# Internal_Power_schematic.net
KiCad netlist of a schematic drawn in Altium Designer
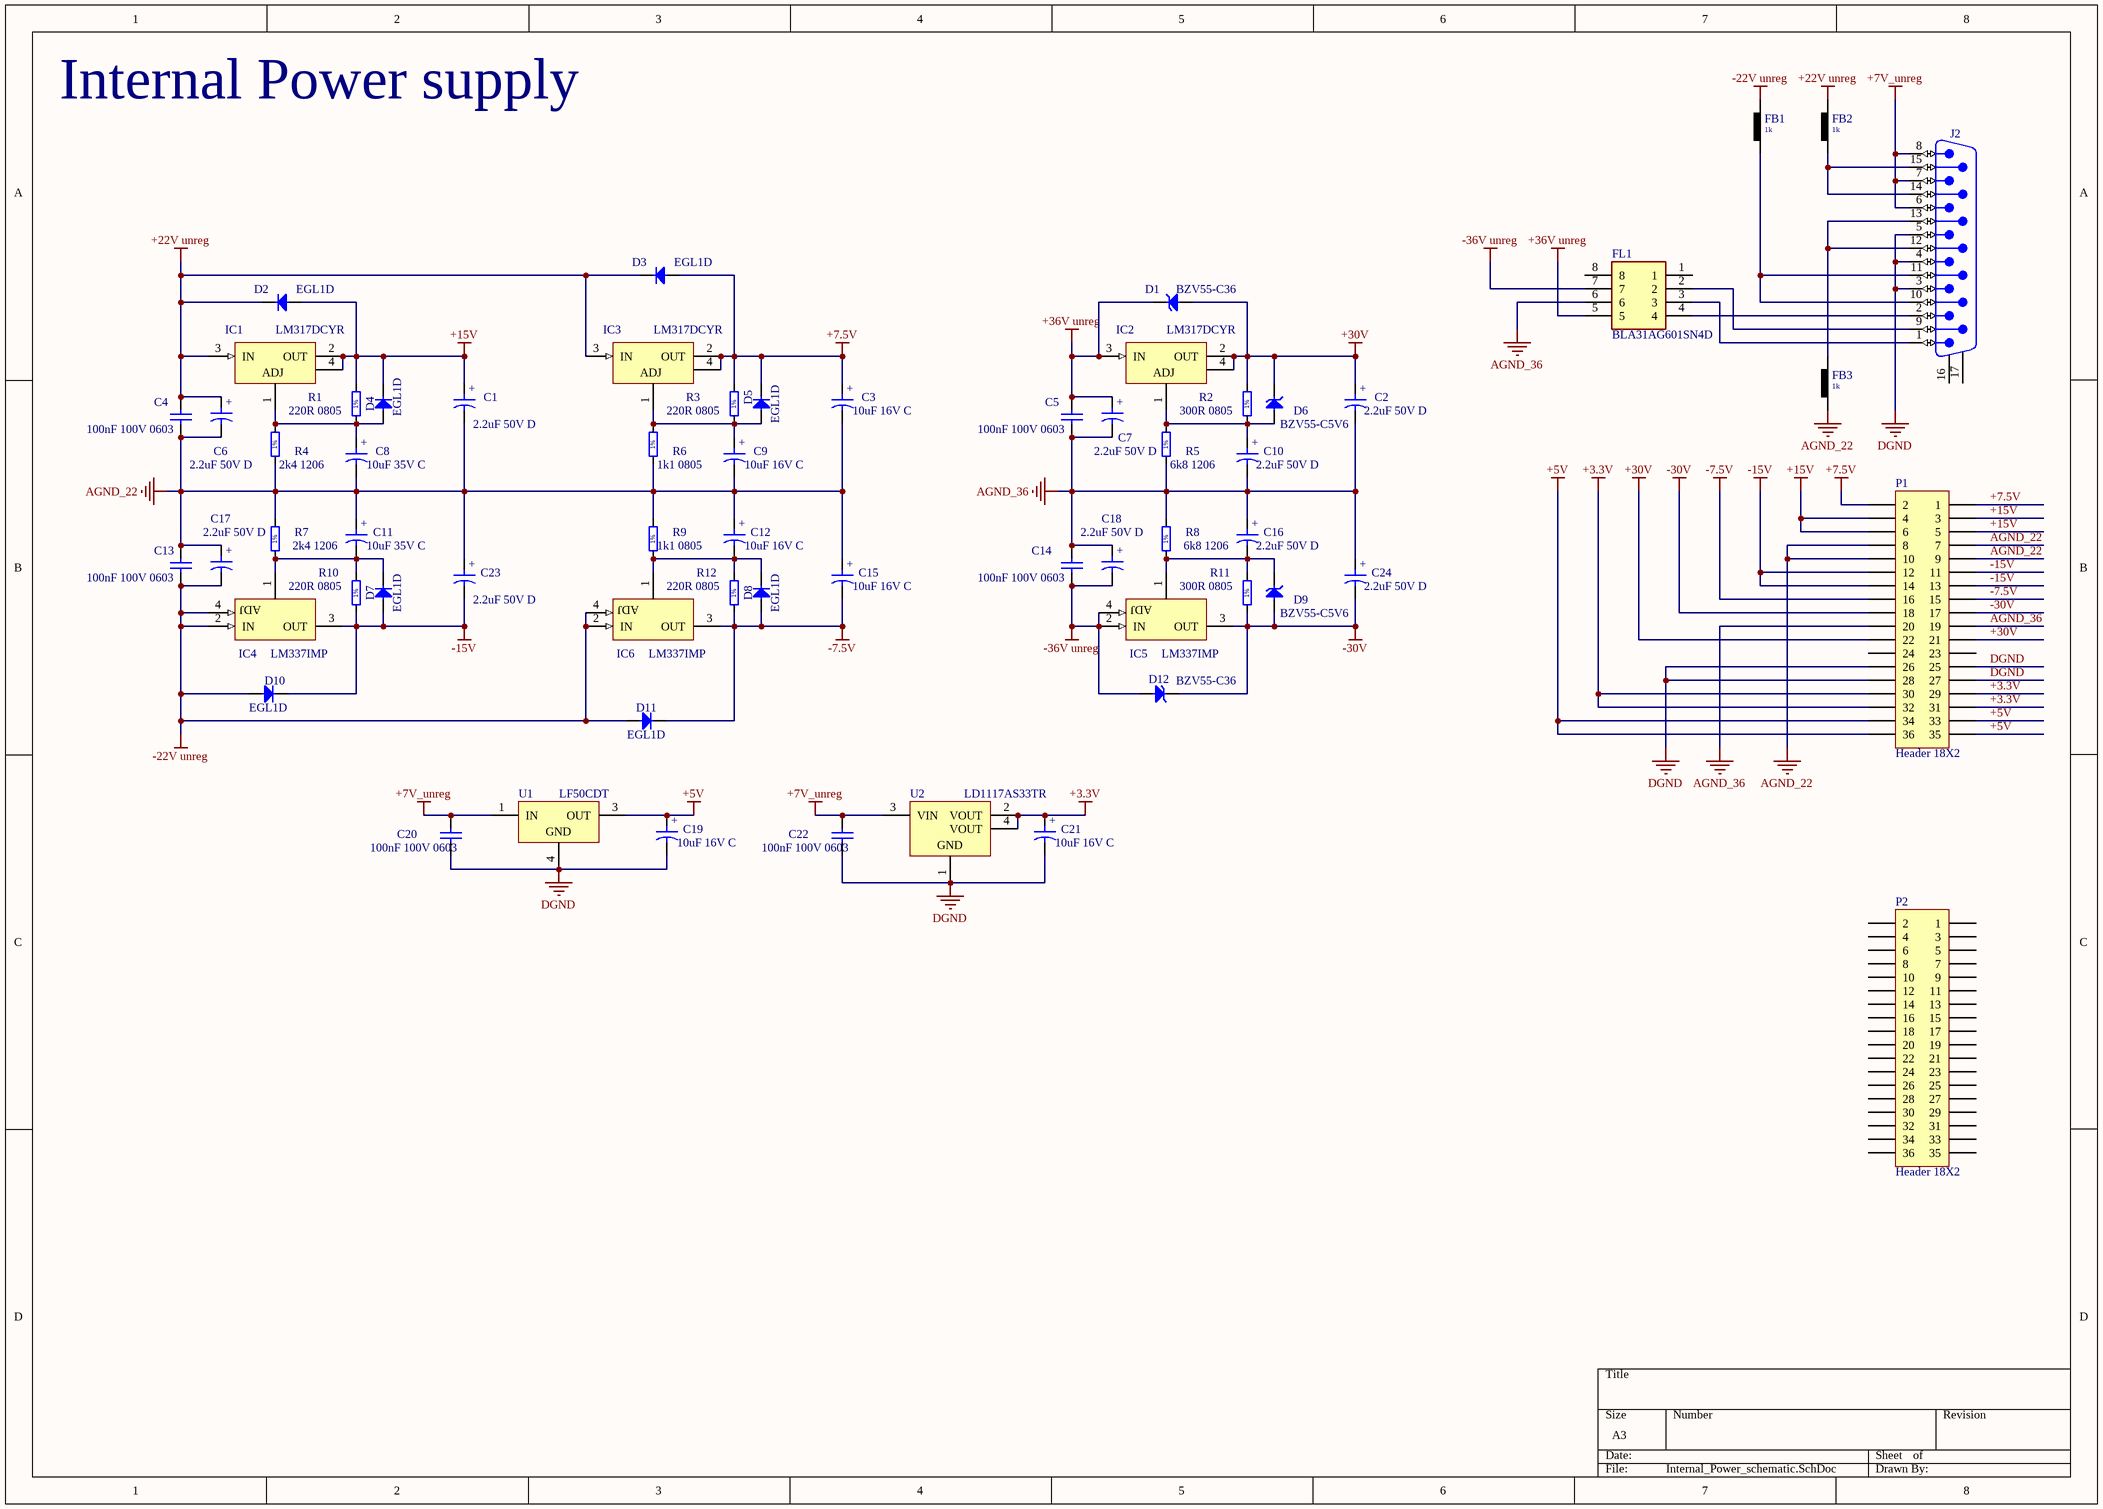
[diagram p0: Internal_Power_schematic.SchDoc]

(export (version "E")
  (design (tool "Eeschema 10.0.6"))
  (components
    (comp (ref "C1")
      (value "2.2uF 50V D")
      (footprint "CAPMP7343X310N")
      (description "Polarised capacitor")
      (fields
        (field (name "PART NUMBER") "CTE7343-31_22UF_35V_20%_LESR0400")
        (field (name "VOLTAGE") "35V")
        (field (name "AUTHOR") "CERN DEM MR")
      )
      (libsource (lib "Capacitors") (part "Capacitor - polarized"))
    )
    (comp (ref "C2")
      (value "2.2uF 50V D")
      (footprint "CAPMP7343X310N")
      (description "Polarised capacitor")
      (fields
        (field (name "PART NUMBER") "CTE7343-31_22UF_35V_20%_LESR0400")
        (field (name "VOLTAGE") "35V")
        (field (name "AUTHOR") "CERN DEM MR")
      )
      (libsource (lib "Capacitors") (part "Capacitor - polarized"))
    )
    (comp (ref "C3")
      (value "10uF 16V C")
      (footprint "CAPMP6032X280N")
      (description "Polarised capacitor")
      (fields
        (field (name "PART NUMBER") "CTE6032-28_10UF_25V_10%_LESR0500")
        (field (name "VOLTAGE") "25V")
        (field (name "AUTHOR") "CERN DEM JLC")
      )
      (libsource (lib "Capacitors") (part "Capacitor - polarized"))
    )
    (comp (ref "C4")
      (value "100nF 100V 0603")
      (footprint "1608[0603]_CAP")
      (description "Capacitor (Semiconductor SIM Model)")
      (fields (field (name "PUBLISHER") "Altium Limited"))
      (libsource (lib "Miscellaneous Devices") (part "Cap Semi"))
    )
    (comp (ref "C5")
      (value "100nF 100V 0603")
      (footprint "1608[0603]_CAP")
      (description "Capacitor (Semiconductor SIM Model)")
      (fields (field (name "PUBLISHER") "Altium Limited"))
      (libsource (lib "Miscellaneous Devices") (part "Cap Semi"))
    )
    (comp (ref "C6")
      (value "2.2uF 50V D")
      (footprint "CAPMP7343X310N")
      (description "Polarised capacitor")
      (fields
        (field (name "PART NUMBER") "CTE7343-31_22UF_35V_20%_LESR0400")
        (field (name "VOLTAGE") "35V")
        (field (name "AUTHOR") "CERN DEM MR")
      )
      (libsource (lib "Capacitors") (part "Capacitor - polarized"))
    )
    (comp (ref "C7")
      (value "2.2uF 50V D")
      (footprint "CAPMP7343X310N")
      (description "Polarised capacitor")
      (fields
        (field (name "PART NUMBER") "CTE7343-31_22UF_35V_20%_LESR0400")
        (field (name "VOLTAGE") "35V")
        (field (name "AUTHOR") "CERN DEM MR")
      )
      (libsource (lib "Capacitors") (part "Capacitor - polarized"))
    )
    (comp (ref "C8")
      (value "10uF 35V C")
      (footprint "CAPMP6032X280N")
      (description "Polarised capacitor")
      (fields
        (field (name "PART NUMBER") "CTE6032-28_10UF_25V_10%_LESR0500")
        (field (name "VOLTAGE") "25V")
        (field (name "AUTHOR") "CERN DEM JLC")
      )
      (libsource (lib "Capacitors") (part "Capacitor - polarized"))
    )
    (comp (ref "C9")
      (value "10uF 16V C")
      (footprint "CAPMP6032X280N")
      (description "Polarised capacitor")
      (fields
        (field (name "PART NUMBER") "CTE6032-28_10UF_25V_10%_LESR0500")
        (field (name "VOLTAGE") "25V")
        (field (name "AUTHOR") "CERN DEM JLC")
      )
      (libsource (lib "Capacitors") (part "Capacitor - polarized"))
    )
    (comp (ref "C10")
      (value "2.2uF 50V D")
      (footprint "CAPMP7343X310N")
      (description "Polarised capacitor")
      (fields
        (field (name "PART NUMBER") "CTE7343-31_22UF_35V_20%_LESR0400")
        (field (name "VOLTAGE") "35V")
        (field (name "AUTHOR") "CERN DEM MR")
      )
      (libsource (lib "Capacitors") (part "Capacitor - polarized"))
    )
    (comp (ref "C11")
      (value "10uF 35V C")
      (footprint "CAPMP6032X280N")
      (description "Polarised capacitor")
      (fields
        (field (name "PART NUMBER") "CTE6032-28_10UF_25V_10%_LESR0500")
        (field (name "VOLTAGE") "25V")
        (field (name "AUTHOR") "CERN DEM JLC")
      )
      (libsource (lib "Capacitors") (part "Capacitor - polarized"))
    )
    (comp (ref "C12")
      (value "10uF 16V C")
      (footprint "CAPMP6032X280N")
      (description "Polarised capacitor")
      (fields
        (field (name "PART NUMBER") "CTE6032-28_10UF_25V_10%_LESR0500")
        (field (name "VOLTAGE") "25V")
        (field (name "AUTHOR") "CERN DEM JLC")
      )
      (libsource (lib "Capacitors") (part "Capacitor - polarized"))
    )
    (comp (ref "C13")
      (value "100nF 100V 0603")
      (footprint "1608[0603]_CAP")
      (description "Capacitor (Semiconductor SIM Model)")
      (fields (field (name "PUBLISHER") "Altium Limited"))
      (libsource (lib "Miscellaneous Devices") (part "Cap Semi"))
    )
    (comp (ref "C14")
      (value "100nF 100V 0603")
      (footprint "1608[0603]_CAP")
      (description "Capacitor (Semiconductor SIM Model)")
      (fields (field (name "PUBLISHER") "Altium Limited"))
      (libsource (lib "Miscellaneous Devices") (part "Cap Semi"))
    )
    (comp (ref "C15")
      (value "10uF 16V C")
      (footprint "CAPMP6032X280N")
      (description "Polarised capacitor")
      (fields
        (field (name "PART NUMBER") "CTE6032-28_10UF_25V_10%_LESR0500")
        (field (name "VOLTAGE") "25V")
        (field (name "AUTHOR") "CERN DEM JLC")
      )
      (libsource (lib "Capacitors") (part "Capacitor - polarized"))
    )
    (comp (ref "C16")
      (value "2.2uF 50V D")
      (footprint "CAPMP7343X310N")
      (description "Polarised capacitor")
      (fields
        (field (name "PART NUMBER") "CTE7343-31_22UF_35V_20%_LESR0400")
        (field (name "VOLTAGE") "35V")
        (field (name "AUTHOR") "CERN DEM MR")
      )
      (libsource (lib "Capacitors") (part "Capacitor - polarized"))
    )
    (comp (ref "C17")
      (value "2.2uF 50V D")
      (footprint "CAPMP7343X310N")
      (description "Polarised capacitor")
      (fields
        (field (name "PART NUMBER") "CTE7343-31_22UF_35V_20%_LESR0400")
        (field (name "VOLTAGE") "35V")
        (field (name "AUTHOR") "CERN DEM MR")
      )
      (libsource (lib "Capacitors") (part "Capacitor - polarized"))
    )
    (comp (ref "C18")
      (value "2.2uF 50V D")
      (footprint "CAPMP7343X310N")
      (description "Polarised capacitor")
      (fields
        (field (name "PART NUMBER") "CTE7343-31_22UF_35V_20%_LESR0400")
        (field (name "VOLTAGE") "35V")
        (field (name "AUTHOR") "CERN DEM MR")
      )
      (libsource (lib "Capacitors") (part "Capacitor - polarized"))
    )
    (comp (ref "C19")
      (value "10uF 16V C")
      (footprint "CAPMP6032X280N")
      (description "Polarised capacitor")
      (fields
        (field (name "PART NUMBER") "CTE6032-28_10UF_25V_10%_LESR0500")
        (field (name "VOLTAGE") "25V")
        (field (name "AUTHOR") "CERN DEM JLC")
      )
      (libsource (lib "Capacitors") (part "Capacitor - polarized"))
    )
    (comp (ref "C20")
      (value "100nF 100V 0603")
      (footprint "1608[0603]_CAP")
      (description "Capacitor (Semiconductor SIM Model)")
      (fields (field (name "PUBLISHER") "Altium Limited"))
      (libsource (lib "Miscellaneous Devices") (part "Cap Semi"))
    )
    (comp (ref "C21")
      (value "10uF 16V C")
      (footprint "CAPMP6032X280N")
      (description "Polarised capacitor")
      (fields
        (field (name "PART NUMBER") "CTE6032-28_10UF_25V_10%_LESR0500")
        (field (name "VOLTAGE") "25V")
        (field (name "AUTHOR") "CERN DEM JLC")
      )
      (libsource (lib "Capacitors") (part "Capacitor - polarized"))
    )
    (comp (ref "C22")
      (value "100nF 100V 0603")
      (footprint "1608[0603]_CAP")
      (description "Capacitor (Semiconductor SIM Model)")
      (fields (field (name "PUBLISHER") "Altium Limited"))
      (libsource (lib "Miscellaneous Devices") (part "Cap Semi"))
    )
    (comp (ref "C23")
      (value "2.2uF 50V D")
      (footprint "CAPMP7343X310N")
      (description "Polarised capacitor")
      (fields
        (field (name "PART NUMBER") "CTE7343-31_22UF_35V_20%_LESR0400")
        (field (name "VOLTAGE") "35V")
        (field (name "AUTHOR") "CERN DEM MR")
      )
      (libsource (lib "Capacitors") (part "Capacitor - polarized"))
    )
    (comp (ref "C24")
      (value "2.2uF 50V D")
      (footprint "CAPMP7343X310N")
      (description "Polarised capacitor")
      (fields
        (field (name "PART NUMBER") "CTE7343-31_22UF_35V_20%_LESR0400")
        (field (name "VOLTAGE") "35V")
        (field (name "AUTHOR") "CERN DEM MR")
      )
      (libsource (lib "Capacitors") (part "Capacitor - polarized"))
    )
    (comp (ref "D1")
      (value "BZV55-C36")
      (footprint "DIOMELF3515N")
      (description "Zener Diode")
      (fields
        (field (name "PART NUMBER") "BZV55-C12")
        (field (name "VOLTAGE") "12V")
        (field (name "AUTHOR") "CERN DEM MR")
      )
      (libsource (lib "ICs And Semiconductors") (part "Diode Zener"))
    )
    (comp (ref "D2")
      (value "EGL1D")
      (footprint "DIOMELF3515N")
      (description "Diode")
      (fields
        (field (name "PART NUMBER") "PMLL4148L")
        (field (name "VOLTAGE") "75V")
        (field (name "AUTHOR") "CERN DEM JLC")
      )
      (libsource (lib "ICs And Semiconductors") (part "Diode"))
    )
    (comp (ref "D3")
      (value "EGL1D")
      (footprint "DIOMELF3515N")
      (description "Diode")
      (fields
        (field (name "PART NUMBER") "PMLL4148L")
        (field (name "VOLTAGE") "75V")
        (field (name "AUTHOR") "CERN DEM JLC")
      )
      (libsource (lib "ICs And Semiconductors") (part "Diode"))
    )
    (comp (ref "D4")
      (value "EGL1D")
      (footprint "DIOMELF3515N")
      (description "Diode")
      (fields
        (field (name "PART NUMBER") "PMLL4148L")
        (field (name "VOLTAGE") "75V")
        (field (name "AUTHOR") "CERN DEM JLC")
      )
      (libsource (lib "ICs And Semiconductors") (part "Diode"))
    )
    (comp (ref "D5")
      (value "EGL1D")
      (footprint "DIOMELF3515N")
      (description "Diode")
      (fields
        (field (name "PART NUMBER") "PMLL4148L")
        (field (name "VOLTAGE") "75V")
        (field (name "AUTHOR") "CERN DEM JLC")
      )
      (libsource (lib "ICs And Semiconductors") (part "Diode"))
    )
    (comp (ref "D6")
      (value "BZV55-C5V6")
      (footprint "DIOMELF3515N")
      (description "Zener Diode")
      (fields
        (field (name "PART NUMBER") "BZV55-C12")
        (field (name "VOLTAGE") "12V")
        (field (name "AUTHOR") "CERN DEM MR")
      )
      (libsource (lib "ICs And Semiconductors") (part "Diode Zener"))
    )
    (comp (ref "D7")
      (value "EGL1D")
      (footprint "DIOMELF3515N")
      (description "Diode")
      (fields
        (field (name "PART NUMBER") "PMLL4148L")
        (field (name "VOLTAGE") "75V")
        (field (name "AUTHOR") "CERN DEM JLC")
      )
      (libsource (lib "ICs And Semiconductors") (part "Diode"))
    )
    (comp (ref "D8")
      (value "EGL1D")
      (footprint "DIOMELF3515N")
      (description "Diode")
      (fields
        (field (name "PART NUMBER") "PMLL4148L")
        (field (name "VOLTAGE") "75V")
        (field (name "AUTHOR") "CERN DEM JLC")
      )
      (libsource (lib "ICs And Semiconductors") (part "Diode"))
    )
    (comp (ref "D9")
      (value "BZV55-C5V6")
      (footprint "DIOMELF3515N")
      (description "Zener Diode")
      (fields
        (field (name "PART NUMBER") "BZV55-C12")
        (field (name "VOLTAGE") "12V")
        (field (name "AUTHOR") "CERN DEM MR")
      )
      (libsource (lib "ICs And Semiconductors") (part "Diode Zener"))
    )
    (comp (ref "D10")
      (value "EGL1D")
      (footprint "DIOMELF3515N")
      (description "Diode")
      (fields
        (field (name "PART NUMBER") "PMLL4148L")
        (field (name "VOLTAGE") "75V")
        (field (name "AUTHOR") "CERN DEM JLC")
      )
      (libsource (lib "ICs And Semiconductors") (part "Diode"))
    )
    (comp (ref "D11")
      (value "EGL1D")
      (footprint "DIOMELF3515N")
      (description "Diode")
      (fields
        (field (name "PART NUMBER") "PMLL4148L")
        (field (name "VOLTAGE") "75V")
        (field (name "AUTHOR") "CERN DEM JLC")
      )
      (libsource (lib "ICs And Semiconductors") (part "Diode"))
    )
    (comp (ref "D12")
      (value "BZV55-C36")
      (footprint "DIOMELF3515N")
      (description "Zener Diode")
      (fields
        (field (name "PART NUMBER") "BZV55-C12")
        (field (name "VOLTAGE") "12V")
        (field (name "AUTHOR") "CERN DEM MR")
      )
      (libsource (lib "ICs And Semiconductors") (part "Diode Zener"))
    )
    (comp (ref "FB1")
      (value "1k")
      (footprint "FB1206")
      (description "1206 1.5A 0.08ohm")
      (libsource (lib "SMD-RCL") (part "Chip FB BLM31P"))
    )
    (comp (ref "FB2")
      (value "1k")
      (footprint "FB1206")
      (description "1206 1.5A 0.08ohm")
      (libsource (lib "SMD-RCL") (part "Chip FB BLM31P"))
    )
    (comp (ref "FB3")
      (value "1k")
      (footprint "FB1206")
      (description "1206 1.5A 0.08ohm")
      (libsource (lib "SMD-RCL") (part "Chip FB BLM31P"))
    )
    (comp (ref "FL1")
      (value "BLA31AG601SN4D")
      (footprint "SamacSys:BLA31AG102SN4D")
      (description "Filter")
      (fields (field (name "MOUSER PART NUMBER") "81-BLA3216A601SG4"))
      (libsource (lib "SamacSys") (part "BLA31AG601SN4D"))
    )
    (comp (ref "IC1")
      (value "LM317DCYR")
      (footprint "SOT230P700X180-4N")
      (description "3-Terminal Regulator 1=Adj 2=OUT 3=IN 4=OUT")
      (fields
        (field (name "PART NUMBER") "LM317EMP")
        (field (name "MANUFACTURER") "TEXAS INSTRUMENTS")
        (field (name "AUTHOR") "CERN DEM JLC")
      )
      (libsource (lib "ICs And Semiconductors") (part "REG3+1 1ADJ-2OUT-3IN+4OUT"))
    )
    (comp (ref "IC2")
      (value "LM317DCYR")
      (footprint "SOT230P700X180-4N")
      (description "3-Terminal Regulator 1=Adj 2=OUT 3=IN 4=OUT")
      (fields
        (field (name "PART NUMBER") "LM317EMP")
        (field (name "MANUFACTURER") "TEXAS INSTRUMENTS")
        (field (name "AUTHOR") "CERN DEM JLC")
      )
      (libsource (lib "ICs And Semiconductors") (part "REG3+1 1ADJ-2OUT-3IN+4OUT"))
    )
    (comp (ref "IC3")
      (value "LM317DCYR")
      (footprint "SOT230P700X180-4N")
      (description "3-Terminal Regulator 1=Adj 2=OUT 3=IN 4=OUT")
      (fields
        (field (name "PART NUMBER") "LM317EMP")
        (field (name "MANUFACTURER") "TEXAS INSTRUMENTS")
        (field (name "AUTHOR") "CERN DEM JLC")
      )
      (libsource (lib "ICs And Semiconductors") (part "REG3+1 1ADJ-2OUT-3IN+4OUT"))
    )
    (comp (ref "IC4")
      (value "LM337IMP")
      (footprint "SOT230P700X180-4N")
      (description "3-Terminal Regulator 1=Adj 2=IN 3=OUT 4=IN")
      (fields
        (field (name "PART NUMBER") "LM337IMP/NOPB")
        (field (name "MANUFACTURER") "TEXAS INSTRUMENTS")
        (field (name "AUTHOR") "CERN DEM JLC")
      )
      (libsource (lib "ICs And Semiconductors") (part "REG3+1 1ADJ-2IN-3OUT+4IN"))
    )
    (comp (ref "IC5")
      (value "LM337IMP")
      (footprint "SOT230P700X180-4N")
      (description "3-Terminal Regulator 1=Adj 2=IN 3=OUT 4=IN")
      (fields
        (field (name "PART NUMBER") "LM337IMP/NOPB")
        (field (name "MANUFACTURER") "TEXAS INSTRUMENTS")
        (field (name "AUTHOR") "CERN DEM JLC")
      )
      (libsource (lib "ICs And Semiconductors") (part "REG3+1 1ADJ-2IN-3OUT+4IN"))
    )
    (comp (ref "IC6")
      (value "LM337IMP")
      (footprint "SOT230P700X180-4N")
      (description "3-Terminal Regulator 1=Adj 2=IN 3=OUT 4=IN")
      (fields
        (field (name "PART NUMBER") "LM337IMP/NOPB")
        (field (name "MANUFACTURER") "TEXAS INSTRUMENTS")
        (field (name "AUTHOR") "CERN DEM JLC")
      )
      (libsource (lib "ICs And Semiconductors") (part "REG3+1 1ADJ-2IN-3OUT+4IN"))
    )
    (comp (ref "J2")
      (value "D-Sub")
      (footprint "DB15_PCB_AL;UMINIUM")
      (description "Connector D-sub 15 Male")
      (fields
        (field (name "PART NUMBER") "AMPHENOL_L117DFA15P1ATN")
        (field (name "MANUFACTURER") "AMPHENOL")
        (field (name "AUTHOR") "CERN DEM JLC")
      )
      (libsource (lib "Connectors") (part "Connector D-sub 15 Male"))
    )
    (comp (ref "P1")
      (value "Header 18X2")
      (footprint "18x2 header aluminium")
      (description "Header, 18-Pin, Dual row")
      (fields (field (name "PUBLISHER") "Altium Limited"))
      (libsource (lib "Miscellaneous Connectors") (part "Header 18X2"))
    )
    (comp (ref "P2")
      (value "Header 18X2")
      (footprint "18x2 header aluminium")
      (description "Header, 18-Pin, Dual row")
      (fields (field (name "PUBLISHER") "Altium Limited"))
      (libsource (lib "Miscellaneous Connectors") (part "Header 18X2"))
    )
    (comp (ref "R1")
      (value "220R 0805")
      (footprint "RESC2012X60N")
      (description "Resistor - 1%")
      (fields
        (field (name "PART NUMBER") "R0805_220R_1%_0.125W_100PPM")
        (field (name "POWER") "0.125W")
        (field (name "AUTHOR") "CERN DEM JLC")
      )
      (libsource (lib "Resistors") (part "Resistor - 1%"))
    )
    (comp (ref "R2")
      (value "300R 0805")
      (footprint "RESC2012X60N")
      (description "Resistor - 1%")
      (fields
        (field (name "PART NUMBER") "R0805_220R_1%_0.125W_100PPM")
        (field (name "POWER") "0.125W")
        (field (name "AUTHOR") "CERN DEM JLC")
      )
      (libsource (lib "Resistors") (part "Resistor - 1%"))
    )
    (comp (ref "R3")
      (value "220R 0805")
      (footprint "RESC2012X60N")
      (description "Resistor - 1%")
      (fields
        (field (name "PART NUMBER") "R0805_220R_1%_0.125W_100PPM")
        (field (name "POWER") "0.125W")
        (field (name "AUTHOR") "CERN DEM JLC")
      )
      (libsource (lib "Resistors") (part "Resistor - 1%"))
    )
    (comp (ref "R4")
      (value "2k4 1206")
      (footprint "RESC3216X65N")
      (description "Resistor - 1%")
      (fields
        (field (name "PART NUMBER") "R1206_2K4_1%_0.25W_100PPM")
        (field (name "POWER") "0.25W")
        (field (name "AUTHOR") "CERN DEM JLC")
      )
      (libsource (lib "Resistors") (part "Resistor - 1%"))
    )
    (comp (ref "R5")
      (value "6k8 1206")
      (footprint "RESC3216X65N")
      (description "Resistor - 1%")
      (fields
        (field (name "PART NUMBER") "R1206_2K4_1%_0.25W_100PPM")
        (field (name "POWER") "0.25W")
        (field (name "AUTHOR") "CERN DEM JLC")
      )
      (libsource (lib "Resistors") (part "Resistor - 1%"))
    )
    (comp (ref "R6")
      (value "1k1 0805")
      (footprint "RESC2012X60N")
      (description "Resistor - 1%")
      (fields
        (field (name "PART NUMBER") "R0805_1K1_1%_0.125W_100PPM")
        (field (name "POWER") "0.125W")
        (field (name "AUTHOR") "CERN DEM JLC")
      )
      (libsource (lib "Resistors") (part "Resistor - 1%"))
    )
    (comp (ref "R7")
      (value "2k4 1206")
      (footprint "RESC3216X65N")
      (description "Resistor - 1%")
      (fields
        (field (name "PART NUMBER") "R1206_2K4_1%_0.25W_100PPM")
        (field (name "POWER") "0.25W")
        (field (name "AUTHOR") "CERN DEM JLC")
      )
      (libsource (lib "Resistors") (part "Resistor - 1%"))
    )
    (comp (ref "R8")
      (value "6k8 1206")
      (footprint "RESC3216X65N")
      (description "Resistor - 1%")
      (fields
        (field (name "PART NUMBER") "R1206_2K4_1%_0.25W_100PPM")
        (field (name "POWER") "0.25W")
        (field (name "AUTHOR") "CERN DEM JLC")
      )
      (libsource (lib "Resistors") (part "Resistor - 1%"))
    )
    (comp (ref "R9")
      (value "1k1 0805")
      (footprint "RESC2012X60N")
      (description "Resistor - 1%")
      (fields
        (field (name "PART NUMBER") "R0805_1K1_1%_0.125W_100PPM")
        (field (name "POWER") "0.125W")
        (field (name "AUTHOR") "CERN DEM JLC")
      )
      (libsource (lib "Resistors") (part "Resistor - 1%"))
    )
    (comp (ref "R10")
      (value "220R 0805")
      (footprint "RESC2012X60N")
      (description "Resistor - 1%")
      (fields
        (field (name "PART NUMBER") "R0805_220R_1%_0.125W_100PPM")
        (field (name "POWER") "0.125W")
        (field (name "AUTHOR") "CERN DEM JLC")
      )
      (libsource (lib "Resistors") (part "Resistor - 1%"))
    )
    (comp (ref "R11")
      (value "300R 0805")
      (footprint "RESC2012X60N")
      (description "Resistor - 1%")
      (fields
        (field (name "PART NUMBER") "R0805_220R_1%_0.125W_100PPM")
        (field (name "POWER") "0.125W")
        (field (name "AUTHOR") "CERN DEM JLC")
      )
      (libsource (lib "Resistors") (part "Resistor - 1%"))
    )
    (comp (ref "R12")
      (value "220R 0805")
      (footprint "RESC2012X60N")
      (description "Resistor - 1%")
      (fields
        (field (name "PART NUMBER") "R0805_220R_1%_0.125W_100PPM")
        (field (name "POWER") "0.125W")
        (field (name "AUTHOR") "CERN DEM JLC")
      )
      (libsource (lib "Resistors") (part "Resistor - 1%"))
    )
    (comp (ref "U1")
      (value "LF50CDT")
      (footprint "TO-252")
      (description "500mA, Very Low Drop (0.45V) Voltage Regulator")
      (fields (field (name "PUBLISHER") "Altium Limited"))
      (libsource (lib "ST Power Mgt Voltage Regulator") (part "LF50CDT"))
    )
    (comp (ref "U2")
      (value "LD1117AS33TR")
      (footprint "SOT-223_N")
      (description "1A, Low Drop Positive Voltage Regulator, 3.3V, 4-Pin SOT-223, Tape and Reel")
      (libsource (lib "STMicroelectronics Power Management Linear Regulator") (part "LD1117AS33TR"))
    )
  )
  (nets
    (net (code "1") (name "+3.3V") (class "Default")
      (node (ref "C21") (pin "1") (pinfunction "1_1") (pintype "passive"))
      (node (ref "P1") (pin "29") (pinfunction "29_29") (pintype "passive"))
      (node (ref "P1") (pin "30") (pinfunction "30_30") (pintype "passive"))
      (node (ref "P1") (pin "31") (pinfunction "31_31") (pintype "passive"))
      (node (ref "P1") (pin "32") (pinfunction "32_32") (pintype "passive"))
      (node (ref "U2") (pin "2") (pinfunction "VOUT_2") (pintype "power_in"))
      (node (ref "U2") (pin "4") (pinfunction "VOUT_4") (pintype "power_in"))
    )
    (net (code "2") (name "+5V") (class "Default")
      (node (ref "C19") (pin "1") (pinfunction "1_1") (pintype "passive"))
      (node (ref "P1") (pin "33") (pinfunction "33_33") (pintype "passive"))
      (node (ref "P1") (pin "34") (pinfunction "34_34") (pintype "passive"))
      (node (ref "P1") (pin "35") (pinfunction "35_35") (pintype "passive"))
      (node (ref "P1") (pin "36") (pinfunction "36_36") (pintype "passive"))
      (node (ref "U1") (pin "3") (pinfunction "OUT_3") (pintype "power_in"))
    )
    (net (code "3") (name "+7.5V") (class "Default")
      (node (ref "C3") (pin "1") (pinfunction "1_1") (pintype "passive"))
      (node (ref "D3") (pin "2") (pinfunction "A_2") (pintype "passive"))
      (node (ref "D5") (pin "1") (pinfunction "C_1") (pintype "passive"))
      (node (ref "IC3") (pin "2") (pinfunction "OUT_2") (pintype "power_in"))
      (node (ref "IC3") (pin "4") (pinfunction "OUT_4") (pintype "power_in"))
      (node (ref "P1") (pin "1") (pinfunction "1_1") (pintype "passive"))
      (node (ref "P1") (pin "2") (pinfunction "2_2") (pintype "passive"))
      (node (ref "R3") (pin "2") (pinfunction "2_2") (pintype "passive"))
    )
    (net (code "4") (name "+7V_unreg") (class "Default")
      (node (ref "C20") (pin "1") (pinfunction "1_1") (pintype "passive"))
      (node (ref "C22") (pin "1") (pinfunction "1_1") (pintype "passive"))
      (node (ref "J2") (pin "6") (pinfunction "6_6") (pintype "bidirectional"))
      (node (ref "J2") (pin "7") (pinfunction "7_7") (pintype "bidirectional"))
      (node (ref "J2") (pin "8") (pinfunction "8_8") (pintype "bidirectional"))
      (node (ref "U1") (pin "1") (pinfunction "IN_1") (pintype "power_in"))
      (node (ref "U2") (pin "3") (pinfunction "VIN_3") (pintype "power_in"))
    )
    (net (code "5") (name "+15V") (class "Default")
      (node (ref "C1") (pin "1") (pinfunction "1_1") (pintype "passive"))
      (node (ref "D2") (pin "2") (pinfunction "A_2") (pintype "passive"))
      (node (ref "D4") (pin "1") (pinfunction "C_1") (pintype "passive"))
      (node (ref "IC1") (pin "2") (pinfunction "OUT_2") (pintype "power_in"))
      (node (ref "IC1") (pin "4") (pinfunction "OUT_4") (pintype "power_in"))
      (node (ref "P1") (pin "3") (pinfunction "3_3") (pintype "passive"))
      (node (ref "P1") (pin "4") (pinfunction "4_4") (pintype "passive"))
      (node (ref "P1") (pin "5") (pinfunction "5_5") (pintype "passive"))
      (node (ref "P1") (pin "6") (pinfunction "6_6") (pintype "passive"))
      (node (ref "R1") (pin "2") (pinfunction "2_2") (pintype "passive"))
    )
    (net (code "6") (name "+22V unreg") (class "Default")
      (node (ref "C4") (pin "1") (pinfunction "1_1") (pintype "passive"))
      (node (ref "C6") (pin "1") (pinfunction "1_1") (pintype "passive"))
      (node (ref "D2") (pin "1") (pinfunction "C_1") (pintype "passive"))
      (node (ref "D3") (pin "1") (pinfunction "C_1") (pintype "passive"))
      (node (ref "FB2") (pin "2") (pinfunction "2_2") (pintype "passive"))
      (node (ref "IC1") (pin "3") (pinfunction "IN_3") (pintype "input"))
      (node (ref "IC3") (pin "3") (pinfunction "IN_3") (pintype "input"))
    )
    (net (code "7") (name "+30V") (class "Default")
      (node (ref "C2") (pin "1") (pinfunction "1_1") (pintype "passive"))
      (node (ref "D1") (pin "2") (pinfunction "A_2") (pintype "passive"))
      (node (ref "D6") (pin "1") (pinfunction "C_1") (pintype "passive"))
      (node (ref "IC2") (pin "2") (pinfunction "OUT_2") (pintype "power_in"))
      (node (ref "IC2") (pin "4") (pinfunction "OUT_4") (pintype "power_in"))
      (node (ref "P1") (pin "21") (pinfunction "21_21") (pintype "passive"))
      (node (ref "P1") (pin "22") (pinfunction "22_22") (pintype "passive"))
      (node (ref "R2") (pin "2") (pinfunction "2_2") (pintype "passive"))
    )
    (net (code "8") (name "+36V unreg") (class "Default")
      (node (ref "C5") (pin "1") (pinfunction "1_1") (pintype "passive"))
      (node (ref "C7") (pin "1") (pinfunction "1_1") (pintype "passive"))
      (node (ref "D1") (pin "1") (pinfunction "C_1") (pintype "passive"))
      (node (ref "FL1") (pin "5") (pinfunction "5_5") (pintype "passive"))
      (node (ref "IC2") (pin "3") (pinfunction "IN_3") (pintype "input"))
    )
    (net (code "9") (name "-7.5V") (class "Default")
      (node (ref "C15") (pin "2") (pinfunction "2_2") (pintype "passive"))
      (node (ref "D11") (pin "1") (pinfunction "C_1") (pintype "passive"))
      (node (ref "D8") (pin "2") (pinfunction "A_2") (pintype "passive"))
      (node (ref "IC6") (pin "3") (pinfunction "OUT_3") (pintype "power_in"))
      (node (ref "P1") (pin "15") (pinfunction "15_15") (pintype "passive"))
      (node (ref "P1") (pin "16") (pinfunction "16_16") (pintype "passive"))
      (node (ref "R12") (pin "1") (pinfunction "1_1") (pintype "passive"))
    )
    (net (code "10") (name "-15V") (class "Default")
      (node (ref "C23") (pin "2") (pinfunction "2_2") (pintype "passive"))
      (node (ref "D10") (pin "1") (pinfunction "C_1") (pintype "passive"))
      (node (ref "D7") (pin "2") (pinfunction "A_2") (pintype "passive"))
      (node (ref "IC4") (pin "3") (pinfunction "OUT_3") (pintype "power_in"))
      (node (ref "P1") (pin "11") (pinfunction "11_11") (pintype "passive"))
      (node (ref "P1") (pin "12") (pinfunction "12_12") (pintype "passive"))
      (node (ref "P1") (pin "13") (pinfunction "13_13") (pintype "passive"))
      (node (ref "P1") (pin "14") (pinfunction "14_14") (pintype "passive"))
      (node (ref "R10") (pin "1") (pinfunction "1_1") (pintype "passive"))
    )
    (net (code "11") (name "-22V unreg") (class "Default")
      (node (ref "C13") (pin "2") (pinfunction "2_2") (pintype "passive"))
      (node (ref "C17") (pin "2") (pinfunction "2_2") (pintype "passive"))
      (node (ref "D10") (pin "2") (pinfunction "A_2") (pintype "passive"))
      (node (ref "D11") (pin "2") (pinfunction "A_2") (pintype "passive"))
      (node (ref "FB1") (pin "2") (pinfunction "2_2") (pintype "passive"))
      (node (ref "IC4") (pin "2") (pinfunction "IN_2") (pintype "input"))
      (node (ref "IC4") (pin "4") (pinfunction "IN_4") (pintype "input"))
      (node (ref "IC6") (pin "2") (pinfunction "IN_2") (pintype "input"))
      (node (ref "IC6") (pin "4") (pinfunction "IN_4") (pintype "input"))
    )
    (net (code "12") (name "-30V") (class "Default")
      (node (ref "C24") (pin "2") (pinfunction "2_2") (pintype "passive"))
      (node (ref "D12") (pin "1") (pinfunction "C_1") (pintype "passive"))
      (node (ref "D9") (pin "2") (pinfunction "A_2") (pintype "passive"))
      (node (ref "IC5") (pin "3") (pinfunction "OUT_3") (pintype "power_in"))
      (node (ref "P1") (pin "17") (pinfunction "17_17") (pintype "passive"))
      (node (ref "P1") (pin "18") (pinfunction "18_18") (pintype "passive"))
      (node (ref "R11") (pin "1") (pinfunction "1_1") (pintype "passive"))
    )
    (net (code "13") (name "-36V unreg") (class "Default")
      (node (ref "C14") (pin "2") (pinfunction "2_2") (pintype "passive"))
      (node (ref "C18") (pin "2") (pinfunction "2_2") (pintype "passive"))
      (node (ref "D12") (pin "2") (pinfunction "A_2") (pintype "passive"))
      (node (ref "FL1") (pin "7") (pinfunction "7_7") (pintype "passive"))
      (node (ref "IC5") (pin "2") (pinfunction "IN_2") (pintype "input"))
      (node (ref "IC5") (pin "4") (pinfunction "IN_4") (pintype "input"))
    )
    (net (code "14") (name "AGND_22") (class "Default")
      (node (ref "C1") (pin "2") (pinfunction "2_2") (pintype "passive"))
      (node (ref "C11") (pin "1") (pinfunction "1_1") (pintype "passive"))
      (node (ref "C12") (pin "1") (pinfunction "1_1") (pintype "passive"))
      (node (ref "C13") (pin "1") (pinfunction "1_1") (pintype "passive"))
      (node (ref "C15") (pin "1") (pinfunction "1_1") (pintype "passive"))
      (node (ref "C17") (pin "1") (pinfunction "1_1") (pintype "passive"))
      (node (ref "C23") (pin "1") (pinfunction "1_1") (pintype "passive"))
      (node (ref "C3") (pin "2") (pinfunction "2_2") (pintype "passive"))
      (node (ref "C4") (pin "2") (pinfunction "2_2") (pintype "passive"))
      (node (ref "C6") (pin "2") (pinfunction "2_2") (pintype "passive"))
      (node (ref "C8") (pin "2") (pinfunction "2_2") (pintype "passive"))
      (node (ref "C9") (pin "2") (pinfunction "2_2") (pintype "passive"))
      (node (ref "FB3") (pin "1") (pinfunction "1_1") (pintype "passive"))
      (node (ref "P1") (pin "10") (pinfunction "10_10") (pintype "passive"))
      (node (ref "P1") (pin "7") (pinfunction "7_7") (pintype "passive"))
      (node (ref "P1") (pin "8") (pinfunction "8_8") (pintype "passive"))
      (node (ref "P1") (pin "9") (pinfunction "9_9") (pintype "passive"))
      (node (ref "R4") (pin "1") (pinfunction "1_1") (pintype "passive"))
      (node (ref "R6") (pin "1") (pinfunction "1_1") (pintype "passive"))
      (node (ref "R7") (pin "2") (pinfunction "2_2") (pintype "passive"))
      (node (ref "R9") (pin "2") (pinfunction "2_2") (pintype "passive"))
    )
    (net (code "15") (name "AGND_36") (class "Default")
      (node (ref "C10") (pin "2") (pinfunction "2_2") (pintype "passive"))
      (node (ref "C14") (pin "1") (pinfunction "1_1") (pintype "passive"))
      (node (ref "C16") (pin "1") (pinfunction "1_1") (pintype "passive"))
      (node (ref "C18") (pin "1") (pinfunction "1_1") (pintype "passive"))
      (node (ref "C2") (pin "2") (pinfunction "2_2") (pintype "passive"))
      (node (ref "C24") (pin "1") (pinfunction "1_1") (pintype "passive"))
      (node (ref "C5") (pin "2") (pinfunction "2_2") (pintype "passive"))
      (node (ref "C7") (pin "2") (pinfunction "2_2") (pintype "passive"))
      (node (ref "FL1") (pin "6") (pinfunction "6_6") (pintype "passive"))
      (node (ref "P1") (pin "19") (pinfunction "19_19") (pintype "passive"))
      (node (ref "P1") (pin "20") (pinfunction "20_20") (pintype "passive"))
      (node (ref "R5") (pin "1") (pinfunction "1_1") (pintype "passive"))
      (node (ref "R8") (pin "2") (pinfunction "2_2") (pintype "passive"))
    )
    (net (code "16") (name "DGND") (class "Default")
      (node (ref "C19") (pin "2") (pinfunction "2_2") (pintype "passive"))
      (node (ref "C20") (pin "2") (pinfunction "2_2") (pintype "passive"))
      (node (ref "C21") (pin "2") (pinfunction "2_2") (pintype "passive"))
      (node (ref "C22") (pin "2") (pinfunction "2_2") (pintype "passive"))
      (node (ref "J2") (pin "3") (pinfunction "3_3") (pintype "bidirectional"))
      (node (ref "J2") (pin "4") (pinfunction "4_4") (pintype "bidirectional"))
      (node (ref "J2") (pin "5") (pinfunction "5_5") (pintype "bidirectional"))
      (node (ref "P1") (pin "25") (pinfunction "25_25") (pintype "passive"))
      (node (ref "P1") (pin "26") (pinfunction "26_26") (pintype "passive"))
      (node (ref "P1") (pin "27") (pinfunction "27_27") (pintype "passive"))
      (node (ref "P1") (pin "28") (pinfunction "28_28") (pintype "passive"))
      (node (ref "U1") (pin "4") (pinfunction "GND_4") (pintype "power_in"))
      (node (ref "U2") (pin "1") (pinfunction "GND_1") (pintype "power_in"))
    )
    (net (code "17") (name "Net-(D4-A)") (class "Default")
      (node (ref "C8") (pin "1") (pinfunction "1_1") (pintype "passive"))
      (node (ref "D4") (pin "2") (pinfunction "A_2") (pintype "passive"))
      (node (ref "IC1") (pin "1") (pinfunction "ADJ_1") (pintype "power_in"))
      (node (ref "R1") (pin "1") (pinfunction "1_1") (pintype "passive"))
      (node (ref "R4") (pin "2") (pinfunction "2_2") (pintype "passive"))
    )
    (net (code "18") (name "Net-(D5-A)") (class "Default")
      (node (ref "C9") (pin "1") (pinfunction "1_1") (pintype "passive"))
      (node (ref "D5") (pin "2") (pinfunction "A_2") (pintype "passive"))
      (node (ref "IC3") (pin "1") (pinfunction "ADJ_1") (pintype "power_in"))
      (node (ref "R3") (pin "1") (pinfunction "1_1") (pintype "passive"))
      (node (ref "R6") (pin "2") (pinfunction "2_2") (pintype "passive"))
    )
    (net (code "19") (name "Net-(D6-A)") (class "Default")
      (node (ref "C10") (pin "1") (pinfunction "1_1") (pintype "passive"))
      (node (ref "D6") (pin "2") (pinfunction "A_2") (pintype "passive"))
      (node (ref "IC2") (pin "1") (pinfunction "ADJ_1") (pintype "power_in"))
      (node (ref "R2") (pin "1") (pinfunction "1_1") (pintype "passive"))
      (node (ref "R5") (pin "2") (pinfunction "2_2") (pintype "passive"))
    )
    (net (code "20") (name "Net-(D7-C)") (class "Default")
      (node (ref "C11") (pin "2") (pinfunction "2_2") (pintype "passive"))
      (node (ref "D7") (pin "1") (pinfunction "C_1") (pintype "passive"))
      (node (ref "IC4") (pin "1") (pinfunction "ADJ_1") (pintype "power_in"))
      (node (ref "R10") (pin "2") (pinfunction "2_2") (pintype "passive"))
      (node (ref "R7") (pin "1") (pinfunction "1_1") (pintype "passive"))
    )
    (net (code "21") (name "Net-(D8-C)") (class "Default")
      (node (ref "C12") (pin "2") (pinfunction "2_2") (pintype "passive"))
      (node (ref "D8") (pin "1") (pinfunction "C_1") (pintype "passive"))
      (node (ref "IC6") (pin "1") (pinfunction "ADJ_1") (pintype "power_in"))
      (node (ref "R12") (pin "2") (pinfunction "2_2") (pintype "passive"))
      (node (ref "R9") (pin "1") (pinfunction "1_1") (pintype "passive"))
    )
    (net (code "22") (name "Net-(D9-C)") (class "Default")
      (node (ref "C16") (pin "2") (pinfunction "2_2") (pintype "passive"))
      (node (ref "D9") (pin "1") (pinfunction "C_1") (pintype "passive"))
      (node (ref "IC5") (pin "1") (pinfunction "ADJ_1") (pintype "power_in"))
      (node (ref "R11") (pin "2") (pinfunction "2_2") (pintype "passive"))
      (node (ref "R8") (pin "1") (pinfunction "1_1") (pintype "passive"))
    )
    (net (code "23") (name "Net-(FB1-Pad1)") (class "Default")
      (node (ref "FB1") (pin "1") (pinfunction "1_1") (pintype "passive"))
      (node (ref "J2") (pin "10") (pinfunction "10_10") (pintype "bidirectional"))
      (node (ref "J2") (pin "11") (pinfunction "11_11") (pintype "bidirectional"))
    )
    (net (code "24") (name "Net-(FB2-Pad1)") (class "Default")
      (node (ref "FB2") (pin "1") (pinfunction "1_1") (pintype "passive"))
      (node (ref "J2") (pin "14") (pinfunction "14_14") (pintype "bidirectional"))
      (node (ref "J2") (pin "15") (pinfunction "15_15") (pintype "bidirectional"))
    )
    (net (code "25") (name "Net-(FB3-Pad2)") (class "Default")
      (node (ref "FB3") (pin "2") (pinfunction "2_2") (pintype "passive"))
      (node (ref "J2") (pin "12") (pinfunction "12_12") (pintype "bidirectional"))
      (node (ref "J2") (pin "13") (pinfunction "13_13") (pintype "bidirectional"))
    )
    (net (code "26") (name "Net-(FL1-Pad2)") (class "Default")
      (node (ref "FL1") (pin "2") (pinfunction "2_2") (pintype "passive"))
      (node (ref "J2") (pin "9") (pinfunction "9_9") (pintype "bidirectional"))
    )
    (net (code "27") (name "Net-(FL1-Pad3)") (class "Default")
      (node (ref "FL1") (pin "3") (pinfunction "3_3") (pintype "passive"))
      (node (ref "J2") (pin "1") (pinfunction "1_1") (pintype "bidirectional"))
    )
    (net (code "28") (name "Net-(FL1-Pad4)") (class "Default")
      (node (ref "FL1") (pin "4") (pinfunction "4_4") (pintype "passive"))
      (node (ref "J2") (pin "2") (pinfunction "2_2") (pintype "bidirectional"))
    )
    (net (code "29") (name "unconnected-(FL1-Pad1)") (class "Default")
      (node (ref "FL1") (pin "1") (pinfunction "1_1") (pintype "passive"))
    )
    (net (code "30") (name "unconnected-(FL1-Pad8)") (class "Default")
      (node (ref "FL1") (pin "8") (pinfunction "8_8") (pintype "passive"))
    )
    (net (code "31") (name "unconnected-(J2-Pad16)") (class "Default")
      (node (ref "J2") (pin "16") (pinfunction "16_16") (pintype "passive"))
    )
    (net (code "32") (name "unconnected-(J2-Pad17)") (class "Default")
      (node (ref "J2") (pin "17") (pinfunction "17_17") (pintype "passive"))
    )
    (net (code "33") (name "unconnected-(P1-Pad23)") (class "Default")
      (node (ref "P1") (pin "23") (pinfunction "23_23") (pintype "passive"))
    )
    (net (code "34") (name "unconnected-(P1-Pad24)") (class "Default")
      (node (ref "P1") (pin "24") (pinfunction "24_24") (pintype "passive"))
    )
    (net (code "35") (name "unconnected-(P2-Pad1)") (class "Default")
      (node (ref "P2") (pin "1") (pinfunction "1_1") (pintype "passive"))
    )
    (net (code "36") (name "unconnected-(P2-Pad2)") (class "Default")
      (node (ref "P2") (pin "2") (pinfunction "2_2") (pintype "passive"))
    )
    (net (code "37") (name "unconnected-(P2-Pad3)") (class "Default")
      (node (ref "P2") (pin "3") (pinfunction "3_3") (pintype "passive"))
    )
    (net (code "38") (name "unconnected-(P2-Pad4)") (class "Default")
      (node (ref "P2") (pin "4") (pinfunction "4_4") (pintype "passive"))
    )
    (net (code "39") (name "unconnected-(P2-Pad5)") (class "Default")
      (node (ref "P2") (pin "5") (pinfunction "5_5") (pintype "passive"))
    )
    (net (code "40") (name "unconnected-(P2-Pad6)") (class "Default")
      (node (ref "P2") (pin "6") (pinfunction "6_6") (pintype "passive"))
    )
    (net (code "41") (name "unconnected-(P2-Pad7)") (class "Default")
      (node (ref "P2") (pin "7") (pinfunction "7_7") (pintype "passive"))
    )
    (net (code "42") (name "unconnected-(P2-Pad8)") (class "Default")
      (node (ref "P2") (pin "8") (pinfunction "8_8") (pintype "passive"))
    )
    (net (code "43") (name "unconnected-(P2-Pad9)") (class "Default")
      (node (ref "P2") (pin "9") (pinfunction "9_9") (pintype "passive"))
    )
    (net (code "44") (name "unconnected-(P2-Pad10)") (class "Default")
      (node (ref "P2") (pin "10") (pinfunction "10_10") (pintype "passive"))
    )
    (net (code "45") (name "unconnected-(P2-Pad11)") (class "Default")
      (node (ref "P2") (pin "11") (pinfunction "11_11") (pintype "passive"))
    )
    (net (code "46") (name "unconnected-(P2-Pad12)") (class "Default")
      (node (ref "P2") (pin "12") (pinfunction "12_12") (pintype "passive"))
    )
    (net (code "47") (name "unconnected-(P2-Pad13)") (class "Default")
      (node (ref "P2") (pin "13") (pinfunction "13_13") (pintype "passive"))
    )
    (net (code "48") (name "unconnected-(P2-Pad14)") (class "Default")
      (node (ref "P2") (pin "14") (pinfunction "14_14") (pintype "passive"))
    )
    (net (code "49") (name "unconnected-(P2-Pad15)") (class "Default")
      (node (ref "P2") (pin "15") (pinfunction "15_15") (pintype "passive"))
    )
    (net (code "50") (name "unconnected-(P2-Pad16)") (class "Default")
      (node (ref "P2") (pin "16") (pinfunction "16_16") (pintype "passive"))
    )
    (net (code "51") (name "unconnected-(P2-Pad17)") (class "Default")
      (node (ref "P2") (pin "17") (pinfunction "17_17") (pintype "passive"))
    )
    (net (code "52") (name "unconnected-(P2-Pad18)") (class "Default")
      (node (ref "P2") (pin "18") (pinfunction "18_18") (pintype "passive"))
    )
    (net (code "53") (name "unconnected-(P2-Pad19)") (class "Default")
      (node (ref "P2") (pin "19") (pinfunction "19_19") (pintype "passive"))
    )
    (net (code "54") (name "unconnected-(P2-Pad20)") (class "Default")
      (node (ref "P2") (pin "20") (pinfunction "20_20") (pintype "passive"))
    )
    (net (code "55") (name "unconnected-(P2-Pad21)") (class "Default")
      (node (ref "P2") (pin "21") (pinfunction "21_21") (pintype "passive"))
    )
    (net (code "56") (name "unconnected-(P2-Pad22)") (class "Default")
      (node (ref "P2") (pin "22") (pinfunction "22_22") (pintype "passive"))
    )
    (net (code "57") (name "unconnected-(P2-Pad23)") (class "Default")
      (node (ref "P2") (pin "23") (pinfunction "23_23") (pintype "passive"))
    )
    (net (code "58") (name "unconnected-(P2-Pad24)") (class "Default")
      (node (ref "P2") (pin "24") (pinfunction "24_24") (pintype "passive"))
    )
    (net (code "59") (name "unconnected-(P2-Pad25)") (class "Default")
      (node (ref "P2") (pin "25") (pinfunction "25_25") (pintype "passive"))
    )
    (net (code "60") (name "unconnected-(P2-Pad26)") (class "Default")
      (node (ref "P2") (pin "26") (pinfunction "26_26") (pintype "passive"))
    )
    (net (code "61") (name "unconnected-(P2-Pad27)") (class "Default")
      (node (ref "P2") (pin "27") (pinfunction "27_27") (pintype "passive"))
    )
    (net (code "62") (name "unconnected-(P2-Pad28)") (class "Default")
      (node (ref "P2") (pin "28") (pinfunction "28_28") (pintype "passive"))
    )
    (net (code "63") (name "unconnected-(P2-Pad29)") (class "Default")
      (node (ref "P2") (pin "29") (pinfunction "29_29") (pintype "passive"))
    )
    (net (code "64") (name "unconnected-(P2-Pad30)") (class "Default")
      (node (ref "P2") (pin "30") (pinfunction "30_30") (pintype "passive"))
    )
    (net (code "65") (name "unconnected-(P2-Pad31)") (class "Default")
      (node (ref "P2") (pin "31") (pinfunction "31_31") (pintype "passive"))
    )
    (net (code "66") (name "unconnected-(P2-Pad32)") (class "Default")
      (node (ref "P2") (pin "32") (pinfunction "32_32") (pintype "passive"))
    )
    (net (code "67") (name "unconnected-(P2-Pad33)") (class "Default")
      (node (ref "P2") (pin "33") (pinfunction "33_33") (pintype "passive"))
    )
    (net (code "68") (name "unconnected-(P2-Pad34)") (class "Default")
      (node (ref "P2") (pin "34") (pinfunction "34_34") (pintype "passive"))
    )
    (net (code "69") (name "unconnected-(P2-Pad35)") (class "Default")
      (node (ref "P2") (pin "35") (pinfunction "35_35") (pintype "passive"))
    )
    (net (code "70") (name "unconnected-(P2-Pad36)") (class "Default")
      (node (ref "P2") (pin "36") (pinfunction "36_36") (pintype "passive"))
    )
  )
)
